# mainboard.net
KiCad netlist of a schematic drawn in EAGLE
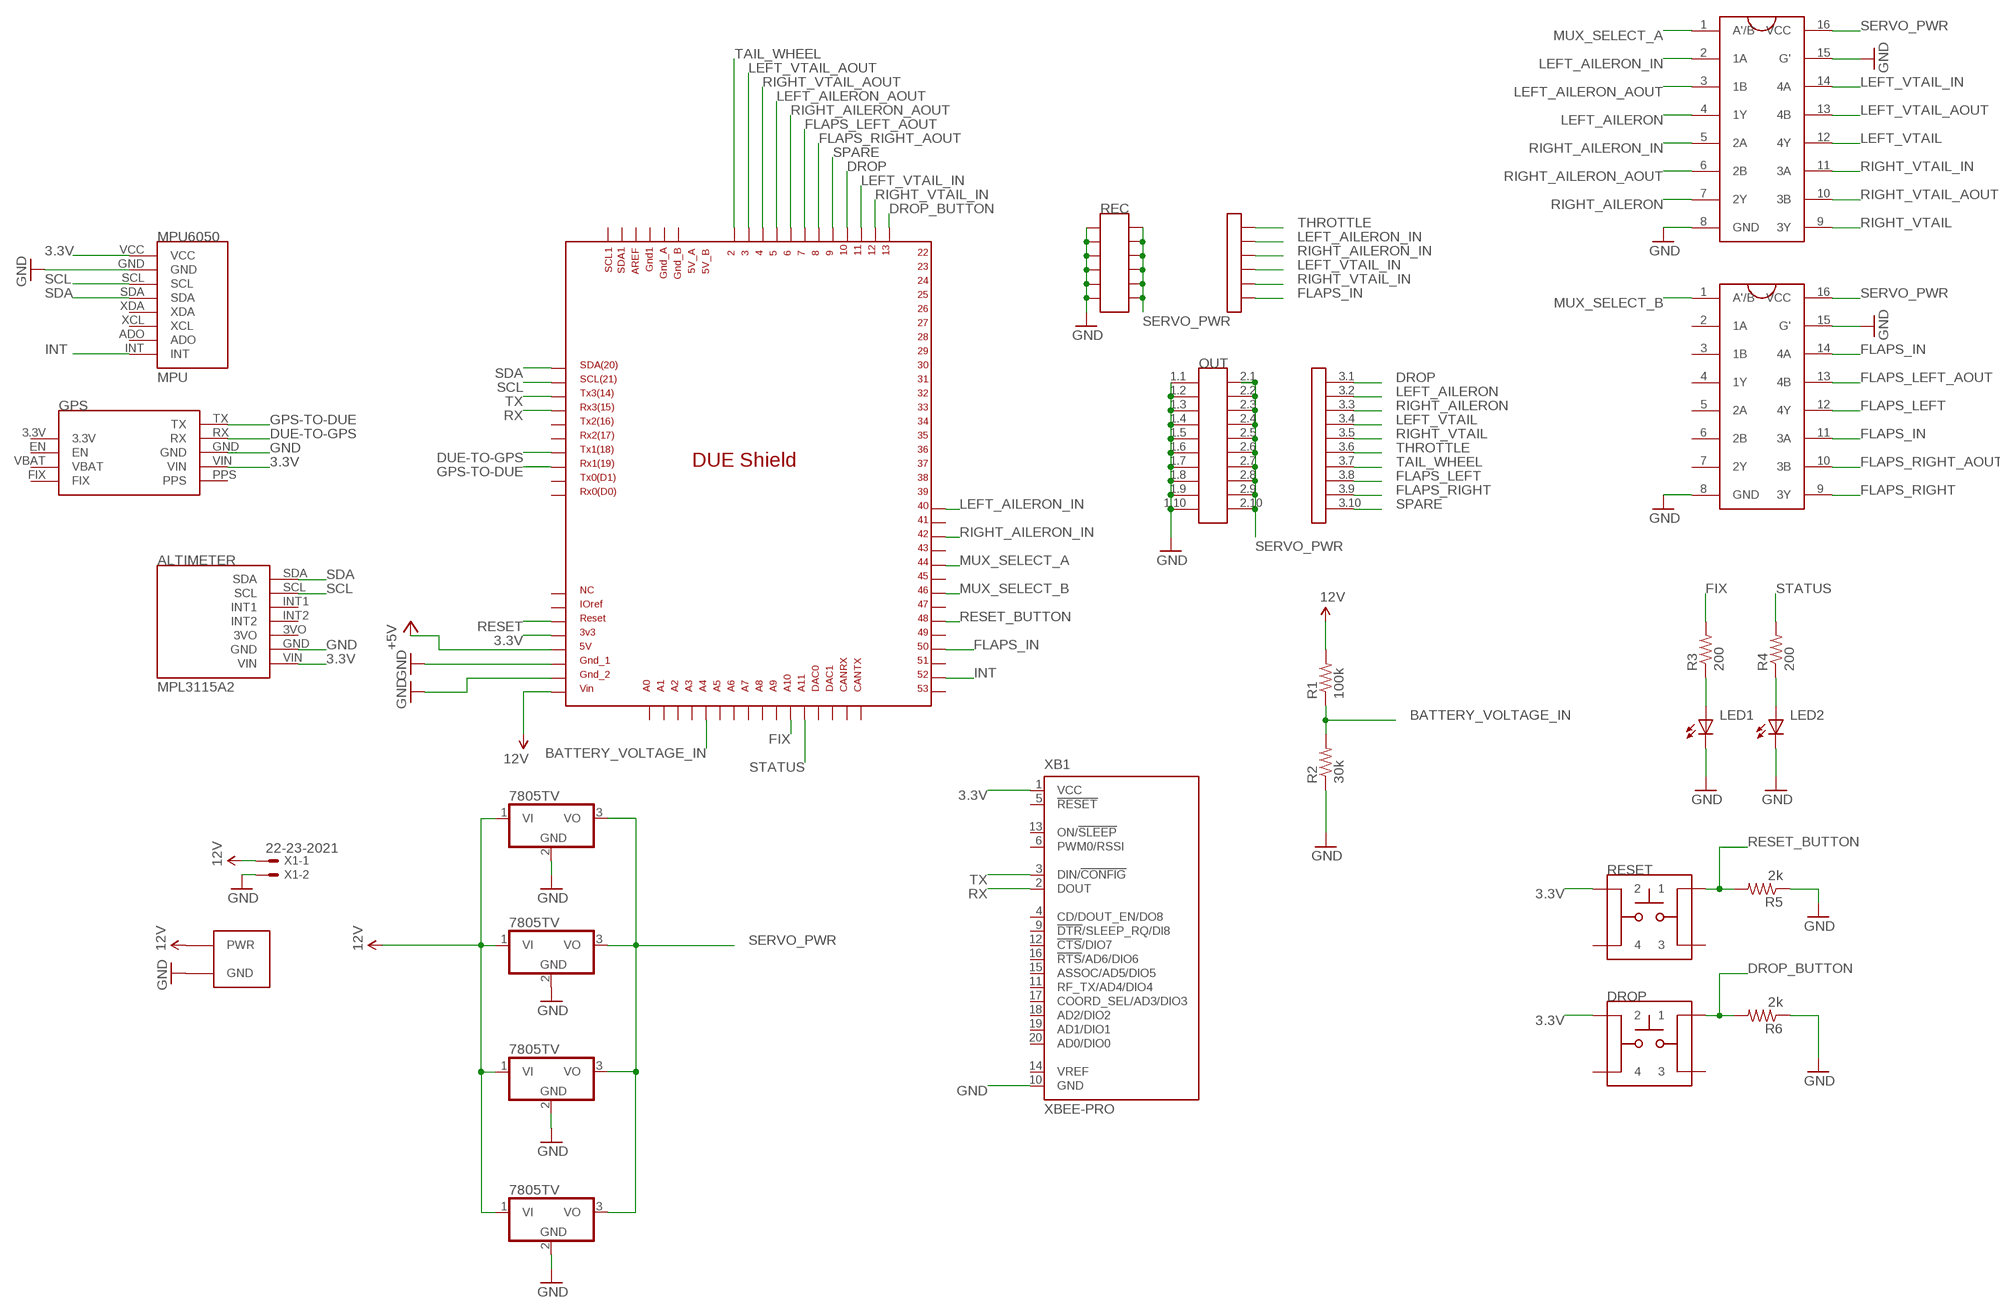
[diagram p0: schematic, sheet 1]

(export (version "E")
  (design (tool "Eeschema 10.0.6"))
  (components
    (comp (ref "DROP")
      (value "PUSHBUTTON")
      (footprint "eagle-import:PUSHBUTTON")
      (libsource (lib "eagle-import") (part "PUSHBUTTON"))
    )
    (comp (ref "G1")
      (value "GPS_ADAFRUIT")
      (footprint "eagle-import:GPS_ADAFRUIT")
      (libsource (lib "eagle-import") (part "GPS_ADAFRUIT"))
    )
    (comp (ref "IC1")
      (value "7805TV")
      (footprint "eagle-import:TO220V")
      (libsource (lib "eagle-import") (part "78TV05"))
    )
    (comp (ref "IC2")
      (value "7805TV")
      (footprint "eagle-import:TO220V")
      (libsource (lib "eagle-import") (part "78TV05"))
    )
    (comp (ref "IC3")
      (value "7805TV")
      (footprint "eagle-import:TO220V")
      (libsource (lib "eagle-import") (part "78TV05"))
    )
    (comp (ref "IC4")
      (value "7805TV")
      (footprint "eagle-import:TO220V")
      (libsource (lib "eagle-import") (part "78TV05"))
    )
    (comp (ref "LED1")
      (value "LED5MM")
      (footprint "eagle-import:LED5MM")
      (libsource (lib "eagle-import") (part "LED5MM"))
    )
    (comp (ref "LED2")
      (value "LED5MM")
      (footprint "eagle-import:LED5MM")
      (libsource (lib "eagle-import") (part "LED5MM"))
    )
    (comp (ref "MPU")
      (value "MPU6050")
      (footprint "eagle-import:MPU6050")
      (libsource (lib "eagle-import") (part "MPU6050"))
    )
    (comp (ref "MUX1")
      (value "SN74HC157")
      (footprint "eagle-import:SN74HC157")
      (libsource (lib "eagle-import") (part "SN74HC157"))
    )
    (comp (ref "MUX2")
      (value "SN74HC157")
      (footprint "eagle-import:SN74HC157")
      (libsource (lib "eagle-import") (part "SN74HC157"))
    )
    (comp (ref "OUT")
      (value "PIN_3X10")
      (footprint "eagle-import:PIN_3X10")
      (libsource (lib "eagle-import") (part "PIN_3X10"))
    )
    (comp (ref "R1")
      (value "100k")
      (footprint "eagle-import:0204_7")
      (libsource (lib "eagle-import") (part "R-US_0204/7"))
    )
    (comp (ref "R2")
      (value "30k")
      (footprint "eagle-import:0204_7")
      (libsource (lib "eagle-import") (part "R-US_0204/7"))
    )
    (comp (ref "R3")
      (value "200")
      (footprint "eagle-import:0204_7")
      (libsource (lib "eagle-import") (part "R-US_0204/7"))
    )
    (comp (ref "R4")
      (value "200")
      (footprint "eagle-import:0204_7")
      (libsource (lib "eagle-import") (part "R-US_0204/7"))
    )
    (comp (ref "R5")
      (value "2k")
      (footprint "eagle-import:0204_7")
      (libsource (lib "eagle-import") (part "R-US_0204/7"))
    )
    (comp (ref "R6")
      (value "2k")
      (footprint "eagle-import:0204_7")
      (libsource (lib "eagle-import") (part "R-US_0204/7"))
    )
    (comp (ref "REC")
      (value "PIN_3X6")
      (footprint "eagle-import:PIN_3X6")
      (libsource (lib "eagle-import") (part "PIN_3X6"))
    )
    (comp (ref "RESET")
      (value "PUSHBUTTON")
      (footprint "eagle-import:PUSHBUTTON")
      (libsource (lib "eagle-import") (part "PUSHBUTTON"))
    )
    (comp (ref "U$1")
      (value "DUE(NORMAL)")
      (footprint "eagle-import:DUE(NORMAL)")
      (libsource (lib "eagle-import") (part "DUE(NORMAL)"))
    )
    (comp (ref "U$3")
      (value "PWR-BATT")
      (footprint "eagle-import:PWR-BATT")
      (libsource (lib "eagle-import") (part "PWR-BATT"))
    )
    (comp (ref "U$4")
      (value "ALTIMETER_V5")
      (footprint "eagle-import:ALTIMETER_V5")
      (libsource (lib "eagle-import") (part "ALTIMETER_V5"))
    )
    (comp (ref "X1")
      (value "22-23-2021")
      (footprint "eagle-import:22-23-2021")
      (fields (field (name "MF") "MOLEX"))
      (libsource (lib "eagle-import") (part "22-23-2021"))
    )
    (comp (ref "XB1")
      (value "XBEE-PRO")
      (footprint "eagle-import:XBEE-PRO")
      (fields (field (name "MPN") "XBP24-AWI-001"))
      (libsource (lib "eagle-import") (part "XBEE-PRO"))
    )
  )
  (nets
    (net (code "1") (name "+5V") (class "Default")
      (node (ref "U$1") (pin "5V") (pinfunction "5V_5V") (pintype "bidirectional"))
    )
    (net (code "2") (name "/3.3V") (class "Default")
      (node (ref "DROP") (pin "2") (pinfunction "2_2") (pintype "bidirectional"))
      (node (ref "G1") (pin "VIN") (pinfunction "VIN_VIN") (pintype "bidirectional"))
      (node (ref "MPU") (pin "VCC") (pinfunction "VCC_VCC") (pintype "bidirectional"))
      (node (ref "RESET") (pin "2") (pinfunction "2_2") (pintype "bidirectional"))
      (node (ref "U$1") (pin "3V3") (pinfunction "3V3_3V3") (pintype "bidirectional"))
      (node (ref "U$4") (pin "VIN") (pinfunction "VIN_VIN") (pintype "bidirectional"))
      (node (ref "XB1") (pin "1") (pinfunction "VCC_1") (pintype "power_in"))
    )
    (net (code "3") (name "/BATTERY_VOLTAGE_IN") (class "Default")
      (node (ref "R1") (pin "1") (pinfunction "1_1") (pintype "passive"))
      (node (ref "R2") (pin "2") (pinfunction "2_2") (pintype "passive"))
      (node (ref "U$1") (pin "A4") (pinfunction "A4_A4") (pintype "bidirectional"))
    )
    (net (code "4") (name "/DROP") (class "Default")
      (node (ref "OUT") (pin "3.1") (pinfunction "3.1_3.1") (pintype "bidirectional"))
      (node (ref "U$1") (pin "10") (pinfunction "10_10") (pintype "bidirectional"))
    )
    (net (code "5") (name "/DROP_BUTTON") (class "Default")
      (node (ref "DROP") (pin "1") (pinfunction "1_1") (pintype "bidirectional"))
      (node (ref "R6") (pin "2") (pinfunction "2_2") (pintype "passive"))
      (node (ref "U$1") (pin "13") (pinfunction "13_13") (pintype "bidirectional"))
    )
    (net (code "6") (name "/DUE-TO-GPS") (class "Default")
      (node (ref "G1") (pin "RX") (pinfunction "RX_RX") (pintype "bidirectional"))
      (node (ref "U$1") (pin "TX1") (pinfunction "TX1_TX1") (pintype "bidirectional"))
    )
    (net (code "7") (name "/FIX") (class "Default")
      (node (ref "R3") (pin "2") (pinfunction "2_2") (pintype "passive"))
      (node (ref "U$1") (pin "A10") (pinfunction "A10_A10") (pintype "bidirectional"))
    )
    (net (code "8") (name "/FLAPS_IN") (class "Default")
      (node (ref "MUX2") (pin "11") (pinfunction "3A_11") (pintype "bidirectional"))
      (node (ref "MUX2") (pin "14") (pinfunction "4A_14") (pintype "bidirectional"))
      (node (ref "REC") (pin "3.6") (pinfunction "3.6_3.6") (pintype "bidirectional"))
      (node (ref "U$1") (pin "50") (pinfunction "50_50") (pintype "bidirectional"))
    )
    (net (code "9") (name "/FLAPS_LEFT") (class "Default")
      (node (ref "MUX2") (pin "12") (pinfunction "4Y_12") (pintype "bidirectional"))
      (node (ref "OUT") (pin "3.8") (pinfunction "3.8_3.8") (pintype "bidirectional"))
    )
    (net (code "10") (name "/FLAPS_LEFT_AOUT") (class "Default")
      (node (ref "MUX2") (pin "13") (pinfunction "4B_13") (pintype "bidirectional"))
      (node (ref "U$1") (pin "7") (pinfunction "7_7") (pintype "bidirectional"))
    )
    (net (code "11") (name "/FLAPS_RIGHT") (class "Default")
      (node (ref "MUX2") (pin "9") (pinfunction "3Y_9") (pintype "bidirectional"))
      (node (ref "OUT") (pin "3.9") (pinfunction "3.9_3.9") (pintype "bidirectional"))
    )
    (net (code "12") (name "/FLAPS_RIGHT_AOUT") (class "Default")
      (node (ref "MUX2") (pin "10") (pinfunction "3B_10") (pintype "bidirectional"))
      (node (ref "U$1") (pin "8") (pinfunction "8_8") (pintype "bidirectional"))
    )
    (net (code "13") (name "/GPS-TO-DUE") (class "Default")
      (node (ref "G1") (pin "TX") (pinfunction "TX_TX") (pintype "bidirectional"))
      (node (ref "U$1") (pin "RX1") (pinfunction "RX1_RX1") (pintype "bidirectional"))
    )
    (net (code "14") (name "/INT") (class "Default")
      (node (ref "MPU") (pin "INT") (pinfunction "INT_INT") (pintype "bidirectional"))
      (node (ref "U$1") (pin "52") (pinfunction "52_52") (pintype "bidirectional"))
    )
    (net (code "15") (name "/LEFT_AILERON") (class "Default")
      (node (ref "MUX1") (pin "4") (pinfunction "1Y_4") (pintype "bidirectional"))
      (node (ref "OUT") (pin "3.2") (pinfunction "3.2_3.2") (pintype "bidirectional"))
    )
    (net (code "16") (name "/LEFT_AILERON_AOUT") (class "Default")
      (node (ref "MUX1") (pin "3") (pinfunction "1B_3") (pintype "bidirectional"))
      (node (ref "U$1") (pin "5") (pinfunction "5_5") (pintype "bidirectional"))
    )
    (net (code "17") (name "/LEFT_AILERON_IN") (class "Default")
      (node (ref "MUX1") (pin "2") (pinfunction "1A_2") (pintype "bidirectional"))
      (node (ref "REC") (pin "3.2") (pinfunction "3.2_3.2") (pintype "bidirectional"))
      (node (ref "U$1") (pin "40") (pinfunction "40_40") (pintype "bidirectional"))
    )
    (net (code "18") (name "/LEFT_VTAIL") (class "Default")
      (node (ref "MUX1") (pin "12") (pinfunction "4Y_12") (pintype "bidirectional"))
      (node (ref "OUT") (pin "3.4") (pinfunction "3.4_3.4") (pintype "bidirectional"))
    )
    (net (code "19") (name "/LEFT_VTAIL_AOUT") (class "Default")
      (node (ref "MUX1") (pin "13") (pinfunction "4B_13") (pintype "bidirectional"))
      (node (ref "U$1") (pin "3") (pinfunction "3_3") (pintype "bidirectional"))
    )
    (net (code "20") (name "/LEFT_VTAIL_IN") (class "Default")
      (node (ref "MUX1") (pin "14") (pinfunction "4A_14") (pintype "bidirectional"))
      (node (ref "REC") (pin "3.4") (pinfunction "3.4_3.4") (pintype "bidirectional"))
      (node (ref "U$1") (pin "11") (pinfunction "11_11") (pintype "bidirectional"))
    )
    (net (code "21") (name "/MUX_SELECT_A") (class "Default")
      (node (ref "MUX1") (pin "1") (pinfunction "A'/B_1") (pintype "bidirectional"))
      (node (ref "U$1") (pin "44") (pinfunction "44_44") (pintype "bidirectional"))
    )
    (net (code "22") (name "/MUX_SELECT_B") (class "Default")
      (node (ref "MUX2") (pin "1") (pinfunction "A'/B_1") (pintype "bidirectional"))
      (node (ref "U$1") (pin "46") (pinfunction "46_46") (pintype "bidirectional"))
    )
    (net (code "23") (name "/RESET") (class "Default")
      (node (ref "U$1") (pin "RESET") (pinfunction "RESET_RESET") (pintype "bidirectional"))
    )
    (net (code "24") (name "/RESET_BUTTON") (class "Default")
      (node (ref "R5") (pin "2") (pinfunction "2_2") (pintype "passive"))
      (node (ref "RESET") (pin "1") (pinfunction "1_1") (pintype "bidirectional"))
      (node (ref "U$1") (pin "48") (pinfunction "48_48") (pintype "bidirectional"))
    )
    (net (code "25") (name "/RIGHT_AILERON") (class "Default")
      (node (ref "MUX1") (pin "7") (pinfunction "2Y_7") (pintype "bidirectional"))
      (node (ref "OUT") (pin "3.3") (pinfunction "3.3_3.3") (pintype "bidirectional"))
    )
    (net (code "26") (name "/RIGHT_AILERON_AOUT") (class "Default")
      (node (ref "MUX1") (pin "6") (pinfunction "2B_6") (pintype "bidirectional"))
      (node (ref "U$1") (pin "6") (pinfunction "6_6") (pintype "bidirectional"))
    )
    (net (code "27") (name "/RIGHT_AILERON_IN") (class "Default")
      (node (ref "MUX1") (pin "5") (pinfunction "2A_5") (pintype "bidirectional"))
      (node (ref "REC") (pin "3.3") (pinfunction "3.3_3.3") (pintype "bidirectional"))
      (node (ref "U$1") (pin "42") (pinfunction "42_42") (pintype "bidirectional"))
    )
    (net (code "28") (name "/RIGHT_VTAIL") (class "Default")
      (node (ref "MUX1") (pin "9") (pinfunction "3Y_9") (pintype "bidirectional"))
      (node (ref "OUT") (pin "3.5") (pinfunction "3.5_3.5") (pintype "bidirectional"))
    )
    (net (code "29") (name "/RIGHT_VTAIL_AOUT") (class "Default")
      (node (ref "MUX1") (pin "10") (pinfunction "3B_10") (pintype "bidirectional"))
      (node (ref "U$1") (pin "4") (pinfunction "4_4") (pintype "bidirectional"))
    )
    (net (code "30") (name "/RIGHT_VTAIL_IN") (class "Default")
      (node (ref "MUX1") (pin "11") (pinfunction "3A_11") (pintype "bidirectional"))
      (node (ref "REC") (pin "3.5") (pinfunction "3.5_3.5") (pintype "bidirectional"))
      (node (ref "U$1") (pin "12") (pinfunction "12_12") (pintype "bidirectional"))
    )
    (net (code "31") (name "/RX") (class "Default")
      (node (ref "U$1") (pin "RX3") (pinfunction "RX3_RX3") (pintype "bidirectional"))
      (node (ref "XB1") (pin "2") (pinfunction "DOUT_2") (pintype "output"))
    )
    (net (code "32") (name "/SCL") (class "Default")
      (node (ref "MPU") (pin "SCL") (pinfunction "SCL_SCL") (pintype "bidirectional"))
      (node (ref "U$1") (pin "SCL") (pinfunction "SCL_SCL") (pintype "bidirectional"))
      (node (ref "U$4") (pin "SCL") (pinfunction "SCL_SCL") (pintype "bidirectional"))
    )
    (net (code "33") (name "/SDA") (class "Default")
      (node (ref "MPU") (pin "SDA") (pinfunction "SDA_SDA") (pintype "bidirectional"))
      (node (ref "U$1") (pin "SDA") (pinfunction "SDA_SDA") (pintype "bidirectional"))
      (node (ref "U$4") (pin "SDA") (pinfunction "SDA_SDA") (pintype "bidirectional"))
    )
    (net (code "34") (name "/SERVO_PWR") (class "Default")
      (node (ref "IC1") (pin "3") (pinfunction "VO_3") (pintype "passive"))
      (node (ref "IC2") (pin "3") (pinfunction "VO_3") (pintype "passive"))
      (node (ref "IC3") (pin "3") (pinfunction "VO_3") (pintype "passive"))
      (node (ref "IC4") (pin "3") (pinfunction "VO_3") (pintype "passive"))
      (node (ref "MUX1") (pin "16") (pinfunction "VCC_16") (pintype "bidirectional"))
      (node (ref "MUX2") (pin "16") (pinfunction "VCC_16") (pintype "bidirectional"))
      (node (ref "OUT") (pin "2.1") (pinfunction "2.1_2.1") (pintype "bidirectional"))
      (node (ref "OUT") (pin "2.10") (pinfunction "2.10_2.10") (pintype "bidirectional"))
      (node (ref "OUT") (pin "2.2") (pinfunction "2.2_2.2") (pintype "bidirectional"))
      (node (ref "OUT") (pin "2.3") (pinfunction "2.3_2.3") (pintype "bidirectional"))
      (node (ref "OUT") (pin "2.4") (pinfunction "2.4_2.4") (pintype "bidirectional"))
      (node (ref "OUT") (pin "2.5") (pinfunction "2.5_2.5") (pintype "bidirectional"))
      (node (ref "OUT") (pin "2.6") (pinfunction "2.6_2.6") (pintype "bidirectional"))
      (node (ref "OUT") (pin "2.7") (pinfunction "2.7_2.7") (pintype "bidirectional"))
      (node (ref "OUT") (pin "2.8") (pinfunction "2.8_2.8") (pintype "bidirectional"))
      (node (ref "OUT") (pin "2.9") (pinfunction "2.9_2.9") (pintype "bidirectional"))
      (node (ref "REC") (pin "2.1") (pinfunction "2.1_2.1") (pintype "bidirectional"))
      (node (ref "REC") (pin "2.2") (pinfunction "2.2_2.2") (pintype "bidirectional"))
      (node (ref "REC") (pin "2.3") (pinfunction "2.3_2.3") (pintype "bidirectional"))
      (node (ref "REC") (pin "2.4") (pinfunction "2.4_2.4") (pintype "bidirectional"))
      (node (ref "REC") (pin "2.5") (pinfunction "2.5_2.5") (pintype "bidirectional"))
      (node (ref "REC") (pin "2.6") (pinfunction "2.6_2.6") (pintype "bidirectional"))
    )
    (net (code "35") (name "/SPARE") (class "Default")
      (node (ref "OUT") (pin "3.10") (pinfunction "3.10_3.10") (pintype "bidirectional"))
      (node (ref "U$1") (pin "9") (pinfunction "9_9") (pintype "bidirectional"))
    )
    (net (code "36") (name "/STATUS") (class "Default")
      (node (ref "R4") (pin "2") (pinfunction "2_2") (pintype "passive"))
      (node (ref "U$1") (pin "A11") (pinfunction "A11_A11") (pintype "bidirectional"))
    )
    (net (code "37") (name "/TAIL_WHEEL") (class "Default")
      (node (ref "OUT") (pin "3.7") (pinfunction "3.7_3.7") (pintype "bidirectional"))
      (node (ref "U$1") (pin "2") (pinfunction "2_2") (pintype "bidirectional"))
    )
    (net (code "38") (name "/THROTTLE") (class "Default")
      (node (ref "OUT") (pin "3.6") (pinfunction "3.6_3.6") (pintype "bidirectional"))
      (node (ref "REC") (pin "3.1") (pinfunction "3.1_3.1") (pintype "bidirectional"))
    )
    (net (code "39") (name "/TX") (class "Default")
      (node (ref "U$1") (pin "TX3") (pinfunction "TX3_TX3") (pintype "bidirectional"))
      (node (ref "XB1") (pin "3") (pinfunction "DIN/~{CONFIG}_3") (pintype "input"))
    )
    (net (code "40") (name "12V") (class "Default")
      (node (ref "IC1") (pin "1") (pinfunction "VI_1") (pintype "input"))
      (node (ref "IC2") (pin "1") (pinfunction "VI_1") (pintype "input"))
      (node (ref "IC3") (pin "1") (pinfunction "VI_1") (pintype "input"))
      (node (ref "IC4") (pin "1") (pinfunction "VI_1") (pintype "input"))
      (node (ref "R1") (pin "2") (pinfunction "2_2") (pintype "passive"))
      (node (ref "U$1") (pin "VIN") (pinfunction "VIN_VIN") (pintype "bidirectional"))
      (node (ref "U$3") (pin "PWR") (pinfunction "PWR_PWR") (pintype "bidirectional"))
      (node (ref "X1") (pin "1") (pinfunction "S_1") (pintype "passive"))
    )
    (net (code "41") (name "GND") (class "Default")
      (node (ref "G1") (pin "GND") (pinfunction "GND_GND") (pintype "bidirectional"))
      (node (ref "IC1") (pin "2") (pinfunction "GND_2") (pintype "passive"))
      (node (ref "IC2") (pin "2") (pinfunction "GND_2") (pintype "passive"))
      (node (ref "IC3") (pin "2") (pinfunction "GND_2") (pintype "passive"))
      (node (ref "IC4") (pin "2") (pinfunction "GND_2") (pintype "passive"))
      (node (ref "LED1") (pin "K") (pinfunction "C_K") (pintype "passive"))
      (node (ref "LED2") (pin "K") (pinfunction "C_K") (pintype "passive"))
      (node (ref "MPU") (pin "GND") (pinfunction "GND_GND") (pintype "bidirectional"))
      (node (ref "MUX1") (pin "15") (pinfunction "G'_15") (pintype "bidirectional"))
      (node (ref "MUX1") (pin "8") (pinfunction "GND_8") (pintype "bidirectional"))
      (node (ref "MUX2") (pin "15") (pinfunction "G'_15") (pintype "bidirectional"))
      (node (ref "MUX2") (pin "8") (pinfunction "GND_8") (pintype "bidirectional"))
      (node (ref "OUT") (pin "1.1") (pinfunction "1.1_1.1") (pintype "bidirectional"))
      (node (ref "OUT") (pin "1.10") (pinfunction "1.10_1.10") (pintype "bidirectional"))
      (node (ref "OUT") (pin "1.2") (pinfunction "1.2_1.2") (pintype "bidirectional"))
      (node (ref "OUT") (pin "1.3") (pinfunction "1.3_1.3") (pintype "bidirectional"))
      (node (ref "OUT") (pin "1.4") (pinfunction "1.4_1.4") (pintype "bidirectional"))
      (node (ref "OUT") (pin "1.5") (pinfunction "1.5_1.5") (pintype "bidirectional"))
      (node (ref "OUT") (pin "1.6") (pinfunction "1.6_1.6") (pintype "bidirectional"))
      (node (ref "OUT") (pin "1.7") (pinfunction "1.7_1.7") (pintype "bidirectional"))
      (node (ref "OUT") (pin "1.8") (pinfunction "1.8_1.8") (pintype "bidirectional"))
      (node (ref "OUT") (pin "1.9") (pinfunction "1.9_1.9") (pintype "bidirectional"))
      (node (ref "R2") (pin "1") (pinfunction "1_1") (pintype "passive"))
      (node (ref "R5") (pin "1") (pinfunction "1_1") (pintype "passive"))
      (node (ref "R6") (pin "1") (pinfunction "1_1") (pintype "passive"))
      (node (ref "REC") (pin "1.1") (pinfunction "1.1_1.1") (pintype "bidirectional"))
      (node (ref "REC") (pin "1.2") (pinfunction "1.2_1.2") (pintype "bidirectional"))
      (node (ref "REC") (pin "1.3") (pinfunction "1.3_1.3") (pintype "bidirectional"))
      (node (ref "REC") (pin "1.4") (pinfunction "1.4_1.4") (pintype "bidirectional"))
      (node (ref "REC") (pin "1.5") (pinfunction "1.5_1.5") (pintype "bidirectional"))
      (node (ref "REC") (pin "1.6") (pinfunction "1.6_1.6") (pintype "bidirectional"))
      (node (ref "U$1") (pin "GND_1") (pinfunction "GND_1_GND_1") (pintype "bidirectional"))
      (node (ref "U$1") (pin "GND_2") (pinfunction "GND_2_GND_2") (pintype "bidirectional"))
      (node (ref "U$3") (pin "GND") (pinfunction "GND_GND") (pintype "bidirectional"))
      (node (ref "U$4") (pin "GND") (pinfunction "GND_GND") (pintype "bidirectional"))
      (node (ref "X1") (pin "2") (pinfunction "S_2") (pintype "passive"))
      (node (ref "XB1") (pin "10") (pinfunction "GND_10") (pintype "power_in"))
    )
    (net (code "42") (name "Net-(LED1-PadA)") (class "Default")
      (node (ref "LED1") (pin "A") (pinfunction "A_A") (pintype "passive"))
      (node (ref "R3") (pin "1") (pinfunction "1_1") (pintype "passive"))
    )
    (net (code "43") (name "Net-(LED2-PadA)") (class "Default")
      (node (ref "LED2") (pin "A") (pinfunction "A_A") (pintype "passive"))
      (node (ref "R4") (pin "1") (pinfunction "1_1") (pintype "passive"))
    )
    (net (code "44") (name "unconnected-(DROP-Pad3)") (class "Default")
      (node (ref "DROP") (pin "3") (pinfunction "3_3") (pintype "bidirectional"))
    )
    (net (code "45") (name "unconnected-(DROP-Pad4)") (class "Default")
      (node (ref "DROP") (pin "4") (pinfunction "4_4") (pintype "bidirectional"))
    )
    (net (code "46") (name "unconnected-(G1-Pad3.3V)") (class "Default")
      (node (ref "G1") (pin "3.3V") (pinfunction "3.3V_3.3V") (pintype "bidirectional"))
    )
    (net (code "47") (name "unconnected-(G1-PadEN)") (class "Default")
      (node (ref "G1") (pin "EN") (pinfunction "EN_EN") (pintype "bidirectional"))
    )
    (net (code "48") (name "unconnected-(G1-PadFIX)") (class "Default")
      (node (ref "G1") (pin "FIX") (pinfunction "FIX_FIX") (pintype "bidirectional"))
    )
    (net (code "49") (name "unconnected-(G1-PadPPS)") (class "Default")
      (node (ref "G1") (pin "PPS") (pinfunction "PPS_PPS") (pintype "bidirectional"))
    )
    (net (code "50") (name "unconnected-(G1-PadVBAT)") (class "Default")
      (node (ref "G1") (pin "VBAT") (pinfunction "VBAT_VBAT") (pintype "bidirectional"))
    )
    (net (code "51") (name "unconnected-(MPU-PadADO)") (class "Default")
      (node (ref "MPU") (pin "ADO") (pinfunction "ADO_ADO") (pintype "bidirectional"))
    )
    (net (code "52") (name "unconnected-(MPU-PadXCL)") (class "Default")
      (node (ref "MPU") (pin "XCL") (pinfunction "XCL_XCL") (pintype "bidirectional"))
    )
    (net (code "53") (name "unconnected-(MPU-PadXDA)") (class "Default")
      (node (ref "MPU") (pin "XDA") (pinfunction "XDA_XDA") (pintype "bidirectional"))
    )
    (net (code "54") (name "unconnected-(MUX2-1A-Pad2)") (class "Default")
      (node (ref "MUX2") (pin "2") (pinfunction "1A_2") (pintype "bidirectional"))
    )
    (net (code "55") (name "unconnected-(MUX2-1B-Pad3)") (class "Default")
      (node (ref "MUX2") (pin "3") (pinfunction "1B_3") (pintype "bidirectional"))
    )
    (net (code "56") (name "unconnected-(MUX2-1Y-Pad4)") (class "Default")
      (node (ref "MUX2") (pin "4") (pinfunction "1Y_4") (pintype "bidirectional"))
    )
    (net (code "57") (name "unconnected-(MUX2-2A-Pad5)") (class "Default")
      (node (ref "MUX2") (pin "5") (pinfunction "2A_5") (pintype "bidirectional"))
    )
    (net (code "58") (name "unconnected-(MUX2-2B-Pad6)") (class "Default")
      (node (ref "MUX2") (pin "6") (pinfunction "2B_6") (pintype "bidirectional"))
    )
    (net (code "59") (name "unconnected-(MUX2-2Y-Pad7)") (class "Default")
      (node (ref "MUX2") (pin "7") (pinfunction "2Y_7") (pintype "bidirectional"))
    )
    (net (code "60") (name "unconnected-(RESET-Pad3)") (class "Default")
      (node (ref "RESET") (pin "3") (pinfunction "3_3") (pintype "bidirectional"))
    )
    (net (code "61") (name "unconnected-(RESET-Pad4)") (class "Default")
      (node (ref "RESET") (pin "4") (pinfunction "4_4") (pintype "bidirectional"))
    )
    (net (code "62") (name "unconnected-(U$1-Pad41)") (class "Default")
      (node (ref "U$1") (pin "41") (pinfunction "41_41") (pintype "bidirectional"))
    )
    (net (code "63") (name "unconnected-(U$1-Pad43)") (class "Default")
      (node (ref "U$1") (pin "43") (pinfunction "43_43") (pintype "bidirectional"))
    )
    (net (code "64") (name "unconnected-(U$1-Pad45)") (class "Default")
      (node (ref "U$1") (pin "45") (pinfunction "45_45") (pintype "bidirectional"))
    )
    (net (code "65") (name "unconnected-(U$1-Pad47)") (class "Default")
      (node (ref "U$1") (pin "47") (pinfunction "47_47") (pintype "bidirectional"))
    )
    (net (code "66") (name "unconnected-(U$1-Pad49)") (class "Default")
      (node (ref "U$1") (pin "49") (pinfunction "49_49") (pintype "bidirectional"))
    )
    (net (code "67") (name "unconnected-(U$1-Pad51)") (class "Default")
      (node (ref "U$1") (pin "51") (pinfunction "51_51") (pintype "bidirectional"))
    )
    (net (code "68") (name "unconnected-(U$1-Pad53)") (class "Default")
      (node (ref "U$1") (pin "53") (pinfunction "53_53") (pintype "bidirectional"))
    )
    (net (code "69") (name "unconnected-(U$1-PadA0)") (class "Default")
      (node (ref "U$1") (pin "A0") (pinfunction "A0_A0") (pintype "bidirectional"))
    )
    (net (code "70") (name "unconnected-(U$1-PadA1)") (class "Default")
      (node (ref "U$1") (pin "A1") (pinfunction "A1_A1") (pintype "bidirectional"))
    )
    (net (code "71") (name "unconnected-(U$1-PadA2)") (class "Default")
      (node (ref "U$1") (pin "A2") (pinfunction "A2_A2") (pintype "bidirectional"))
    )
    (net (code "72") (name "unconnected-(U$1-PadA3)") (class "Default")
      (node (ref "U$1") (pin "A3") (pinfunction "A3_A3") (pintype "bidirectional"))
    )
    (net (code "73") (name "unconnected-(U$1-PadA5)") (class "Default")
      (node (ref "U$1") (pin "A5") (pinfunction "A5_A5") (pintype "bidirectional"))
    )
    (net (code "74") (name "unconnected-(U$1-PadA6)") (class "Default")
      (node (ref "U$1") (pin "A6") (pinfunction "A6_A6") (pintype "bidirectional"))
    )
    (net (code "75") (name "unconnected-(U$1-PadA7)") (class "Default")
      (node (ref "U$1") (pin "A7") (pinfunction "A7_A7") (pintype "bidirectional"))
    )
    (net (code "76") (name "unconnected-(U$1-PadA8)") (class "Default")
      (node (ref "U$1") (pin "A8") (pinfunction "A8_A8") (pintype "bidirectional"))
    )
    (net (code "77") (name "unconnected-(U$1-PadA9)") (class "Default")
      (node (ref "U$1") (pin "A9") (pinfunction "A9_A9") (pintype "bidirectional"))
    )
    (net (code "78") (name "unconnected-(U$1-PadAREF)") (class "Default")
      (node (ref "U$1") (pin "AREF") (pinfunction "AREF_AREF") (pintype "bidirectional"))
    )
    (net (code "79") (name "unconnected-(U$1-PadCANRX)") (class "Default")
      (node (ref "U$1") (pin "CANRX") (pinfunction "CANRX_CANRX") (pintype "bidirectional"))
    )
    (net (code "80") (name "unconnected-(U$1-PadCANTX)") (class "Default")
      (node (ref "U$1") (pin "CANTX") (pinfunction "CANTX_CANTX") (pintype "bidirectional"))
    )
    (net (code "81") (name "unconnected-(U$1-PadDAC0)") (class "Default")
      (node (ref "U$1") (pin "DAC0") (pinfunction "DAC0_DAC0") (pintype "bidirectional"))
    )
    (net (code "82") (name "unconnected-(U$1-PadDAC1)") (class "Default")
      (node (ref "U$1") (pin "DAC1") (pinfunction "DAC1_DAC1") (pintype "bidirectional"))
    )
    (net (code "83") (name "unconnected-(U$1-PadGND1)") (class "Default")
      (node (ref "U$1") (pin "GND1") (pinfunction "GND1_GND1") (pintype "bidirectional"))
    )
    (net (code "84") (name "unconnected-(U$1-PadGND_A)") (class "Default")
      (node (ref "U$1") (pin "GND_A") (pinfunction "GND_A_GND_A") (pintype "bidirectional"))
    )
    (net (code "85") (name "unconnected-(U$1-PadGND_B)") (class "Default")
      (node (ref "U$1") (pin "GND_B") (pinfunction "GND_B_GND_B") (pintype "bidirectional"))
    )
    (net (code "86") (name "unconnected-(U$1-PadIOREF)") (class "Default")
      (node (ref "U$1") (pin "IOREF") (pinfunction "IOREF_IOREF") (pintype "bidirectional"))
    )
    (net (code "87") (name "unconnected-(U$1-PadNC)") (class "Default")
      (node (ref "U$1") (pin "NC") (pinfunction "NC_NC") (pintype "bidirectional"))
    )
    (net (code "88") (name "unconnected-(U$1-PadRX0)") (class "Default")
      (node (ref "U$1") (pin "RX0") (pinfunction "RX0_RX0") (pintype "bidirectional"))
    )
    (net (code "89") (name "unconnected-(U$1-PadRX2)") (class "Default")
      (node (ref "U$1") (pin "RX2") (pinfunction "RX2_RX2") (pintype "bidirectional"))
    )
    (net (code "90") (name "unconnected-(U$1-PadSCL1)") (class "Default")
      (node (ref "U$1") (pin "SCL1") (pinfunction "SCL1_SCL1") (pintype "bidirectional"))
    )
    (net (code "91") (name "unconnected-(U$1-PadSDA1)") (class "Default")
      (node (ref "U$1") (pin "SDA1") (pinfunction "SDA1_SDA1") (pintype "bidirectional"))
    )
    (net (code "92") (name "unconnected-(U$1-PadTX0)") (class "Default")
      (node (ref "U$1") (pin "TX0") (pinfunction "TX0_TX0") (pintype "bidirectional"))
    )
    (net (code "93") (name "unconnected-(U$1-PadTX2)") (class "Default")
      (node (ref "U$1") (pin "TX2") (pinfunction "TX2_TX2") (pintype "bidirectional"))
    )
    (net (code "94") (name "unconnected-(U$4-Pad3VO)") (class "Default")
      (node (ref "U$4") (pin "3VO") (pinfunction "3VO_3VO") (pintype "bidirectional"))
    )
    (net (code "95") (name "unconnected-(U$4-PadINT1)") (class "Default")
      (node (ref "U$4") (pin "INT1") (pinfunction "INT1_INT1") (pintype "bidirectional"))
    )
    (net (code "96") (name "unconnected-(U$4-PadINT2)") (class "Default")
      (node (ref "U$4") (pin "INT2") (pinfunction "INT2_INT2") (pintype "bidirectional"))
    )
    (net (code "97") (name "unconnected-(XB1-AD0{slash}DIO0-Pad20)") (class "Default")
      (node (ref "XB1") (pin "20") (pinfunction "AD0/DIO0_20") (pintype "bidirectional"))
    )
    (net (code "98") (name "unconnected-(XB1-AD1{slash}DIO1-Pad19)") (class "Default")
      (node (ref "XB1") (pin "19") (pinfunction "AD1/DIO1_19") (pintype "bidirectional"))
    )
    (net (code "99") (name "unconnected-(XB1-AD2{slash}DIO2-Pad18)") (class "Default")
      (node (ref "XB1") (pin "18") (pinfunction "AD2/DIO2_18") (pintype "bidirectional"))
    )
    (net (code "100") (name "unconnected-(XB1-ASSOC{slash}AD5{slash}DIO5-Pad15)") (class "Default")
      (node (ref "XB1") (pin "15") (pinfunction "ASSOC/AD5/DIO5_15") (pintype "bidirectional"))
    )
    (net (code "101") (name "unconnected-(XB1-CD{slash}DOUT_EN{slash}DO8-Pad4)") (class "Default")
      (node (ref "XB1") (pin "4") (pinfunction "CD/DOUT_EN/DO8_4") (pintype "output"))
    )
    (net (code "102") (name "unconnected-(XB1-COORD_SEL{slash}AD3{slash}DIO3-Pad17)") (class "Default")
      (node (ref "XB1") (pin "17") (pinfunction "COORD_SEL/AD3/DIO3_17") (pintype "bidirectional"))
    )
    (net (code "103") (name "unconnected-(XB1-ON{slash}~{SLEEP}-Pad13)") (class "Default")
      (node (ref "XB1") (pin "13") (pinfunction "ON/~{SLEEP}_13") (pintype "output"))
    )
    (net (code "104") (name "unconnected-(XB1-PWM0{slash}RSSI-Pad6)") (class "Default")
      (node (ref "XB1") (pin "6") (pinfunction "PWM0/RSSI_6") (pintype "output"))
    )
    (net (code "105") (name "unconnected-(XB1-RF_TX{slash}AD4{slash}DIO4-Pad11)") (class "Default")
      (node (ref "XB1") (pin "11") (pinfunction "RF_TX/AD4/DIO4_11") (pintype "bidirectional"))
    )
    (net (code "106") (name "unconnected-(XB1-VREF-Pad14)") (class "Default")
      (node (ref "XB1") (pin "14") (pinfunction "VREF_14") (pintype "input"))
    )
    (net (code "107") (name "unconnected-(XB1-~{CTS}{slash}DIO7-Pad12)") (class "Default")
      (node (ref "XB1") (pin "12") (pinfunction "~{CTS}/DIO7_12") (pintype "bidirectional"))
    )
    (net (code "108") (name "unconnected-(XB1-~{DTR}{slash}SLEEP_RQ{slash}DI8-Pad9)") (class "Default")
      (node (ref "XB1") (pin "9") (pinfunction "~{DTR}/SLEEP_RQ/DI8_9") (pintype "bidirectional"))
    )
    (net (code "109") (name "unconnected-(XB1-~{RESET}-Pad5)") (class "Default")
      (node (ref "XB1") (pin "5") (pinfunction "~{RESET}_5") (pintype "input"))
    )
    (net (code "110") (name "unconnected-(XB1-~{RTS}{slash}AD6{slash}DIO6-Pad16)") (class "Default")
      (node (ref "XB1") (pin "16") (pinfunction "~{RTS}/AD6/DIO6_16") (pintype "bidirectional"))
    )
  )
)
